# base_station.net
KiCad netlist of a schematic drawn in EAGLE
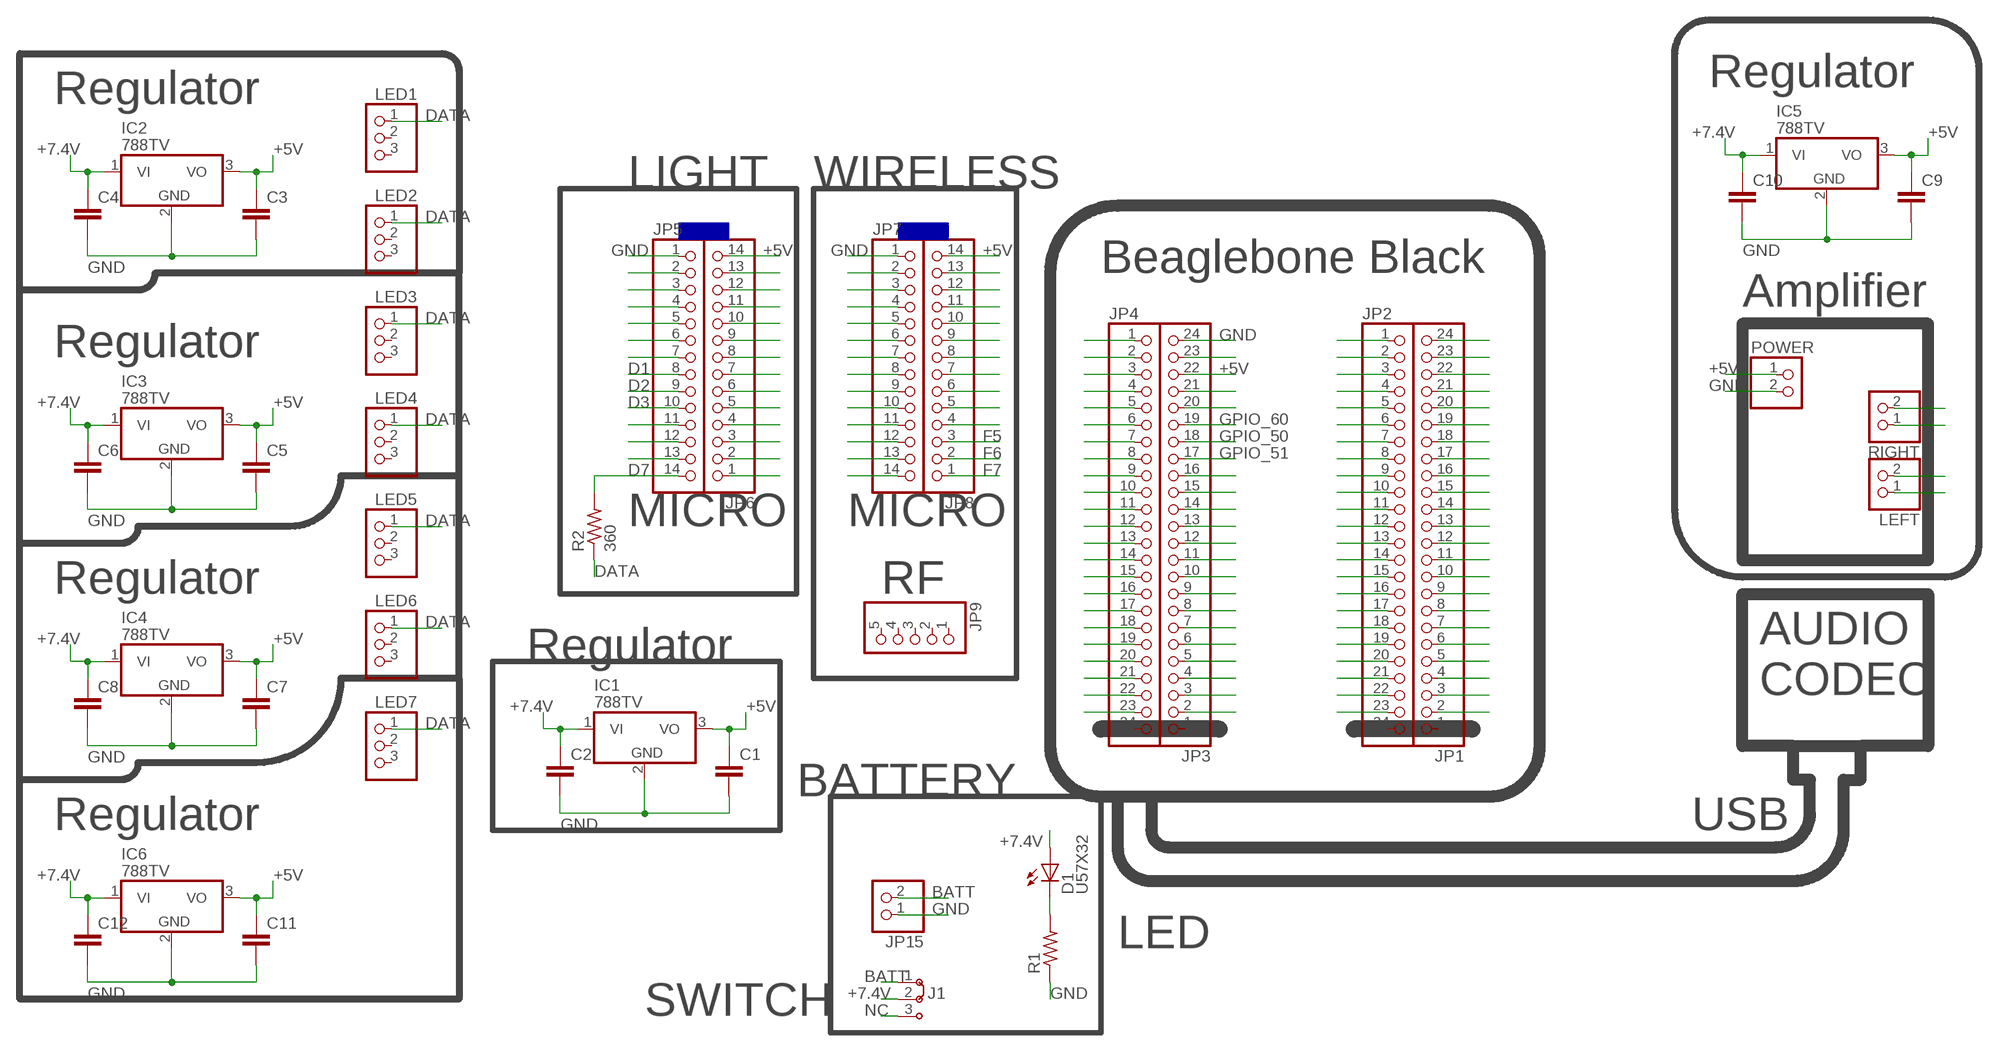
[diagram p0: schematic, sheet 1]

(export (version "E")
  (design (tool "Eeschema 10.0.6"))
  (components
    (comp (ref "C1")
      (value "C2,5-3")
      (footprint "eagle-import:C2.5-3")
      (libsource (lib "eagle-import") (part "C2,5-3"))
    )
    (comp (ref "C2")
      (value "C2,5-3")
      (footprint "eagle-import:C2.5-3")
      (libsource (lib "eagle-import") (part "C2,5-3"))
    )
    (comp (ref "C3")
      (value "C2,5-3")
      (footprint "eagle-import:C2.5-3")
      (libsource (lib "eagle-import") (part "C2,5-3"))
    )
    (comp (ref "C4")
      (value "C2,5-3")
      (footprint "eagle-import:C2.5-3")
      (libsource (lib "eagle-import") (part "C2,5-3"))
    )
    (comp (ref "C5")
      (value "C2,5-3")
      (footprint "eagle-import:C2.5-3")
      (libsource (lib "eagle-import") (part "C2,5-3"))
    )
    (comp (ref "C6")
      (value "C2,5-3")
      (footprint "eagle-import:C2.5-3")
      (libsource (lib "eagle-import") (part "C2,5-3"))
    )
    (comp (ref "C7")
      (value "C2,5-3")
      (footprint "eagle-import:C2.5-3")
      (libsource (lib "eagle-import") (part "C2,5-3"))
    )
    (comp (ref "C8")
      (value "C2,5-3")
      (footprint "eagle-import:C2.5-3")
      (libsource (lib "eagle-import") (part "C2,5-3"))
    )
    (comp (ref "C9")
      (value "C2,5-3")
      (footprint "eagle-import:C2.5-3")
      (libsource (lib "eagle-import") (part "C2,5-3"))
    )
    (comp (ref "C10")
      (value "C2,5-3")
      (footprint "eagle-import:C2.5-3")
      (libsource (lib "eagle-import") (part "C2,5-3"))
    )
    (comp (ref "C11")
      (value "C2,5-3")
      (footprint "eagle-import:C2.5-3")
      (libsource (lib "eagle-import") (part "C2,5-3"))
    )
    (comp (ref "C12")
      (value "C2,5-3")
      (footprint "eagle-import:C2.5-3")
      (libsource (lib "eagle-import") (part "C2,5-3"))
    )
    (comp (ref "D1")
      (value "U57X32")
      (footprint "eagle-import:U57X32")
      (libsource (lib "eagle-import") (part "U57X32"))
    )
    (comp (ref "IC1")
      (value "788TV")
      (footprint "eagle-import:TO220V")
      (libsource (lib "eagle-import") (part "78TV8"))
    )
    (comp (ref "IC2")
      (value "788TV")
      (footprint "eagle-import:TO220V")
      (libsource (lib "eagle-import") (part "78TV8"))
    )
    (comp (ref "IC3")
      (value "788TV")
      (footprint "eagle-import:TO220V")
      (libsource (lib "eagle-import") (part "78TV8"))
    )
    (comp (ref "IC4")
      (value "788TV")
      (footprint "eagle-import:TO220V")
      (libsource (lib "eagle-import") (part "78TV8"))
    )
    (comp (ref "IC5")
      (value "788TV")
      (footprint "eagle-import:TO220V")
      (libsource (lib "eagle-import") (part "78TV8"))
    )
    (comp (ref "IC6")
      (value "788TV")
      (footprint "eagle-import:TO220V")
      (libsource (lib "eagle-import") (part "78TV8"))
    )
    (comp (ref "J1")
      (value "J2X2MM")
      (footprint "eagle-import:04C")
      (libsource (lib "eagle-import") (part "J2X2MM"))
    )
    (comp (ref "JP1")
      (value "PINHD-1X24")
      (footprint "eagle-import:1X24")
      (libsource (lib "eagle-import") (part "PINHD-1X24"))
    )
    (comp (ref "JP2")
      (value "PINHD-1X24")
      (footprint "eagle-import:1X24")
      (libsource (lib "eagle-import") (part "PINHD-1X24"))
    )
    (comp (ref "JP3")
      (value "PINHD-1X24")
      (footprint "eagle-import:1X24")
      (libsource (lib "eagle-import") (part "PINHD-1X24"))
    )
    (comp (ref "JP4")
      (value "PINHD-1X24")
      (footprint "eagle-import:1X24")
      (libsource (lib "eagle-import") (part "PINHD-1X24"))
    )
    (comp (ref "JP5")
      (value "PINHD-1X14")
      (footprint "eagle-import:1X14")
      (libsource (lib "eagle-import") (part "PINHD-1X14"))
    )
    (comp (ref "JP6")
      (value "PINHD-1X14")
      (footprint "eagle-import:1X14")
      (libsource (lib "eagle-import") (part "PINHD-1X14"))
    )
    (comp (ref "JP7")
      (value "PINHD-1X14")
      (footprint "eagle-import:1X14")
      (libsource (lib "eagle-import") (part "PINHD-1X14"))
    )
    (comp (ref "JP8")
      (value "PINHD-1X14")
      (footprint "eagle-import:1X14")
      (libsource (lib "eagle-import") (part "PINHD-1X14"))
    )
    (comp (ref "JP9")
      (value "PINHD-1X5")
      (footprint "eagle-import:1X05")
      (libsource (lib "eagle-import") (part "PINHD-1X5"))
    )
    (comp (ref "JP15")
      (value "PINHD-1X2")
      (footprint "eagle-import:1X02")
      (libsource (lib "eagle-import") (part "PINHD-1X2"))
    )
    (comp (ref "LED1")
      (value "PINHD-1X3")
      (footprint "eagle-import:1X03")
      (libsource (lib "eagle-import") (part "PINHD-1X3"))
    )
    (comp (ref "LED2")
      (value "PINHD-1X3")
      (footprint "eagle-import:1X03")
      (libsource (lib "eagle-import") (part "PINHD-1X3"))
    )
    (comp (ref "LED3")
      (value "PINHD-1X3")
      (footprint "eagle-import:1X03")
      (libsource (lib "eagle-import") (part "PINHD-1X3"))
    )
    (comp (ref "LED4")
      (value "PINHD-1X3")
      (footprint "eagle-import:1X03")
      (libsource (lib "eagle-import") (part "PINHD-1X3"))
    )
    (comp (ref "LED5")
      (value "PINHD-1X3")
      (footprint "eagle-import:1X03")
      (libsource (lib "eagle-import") (part "PINHD-1X3"))
    )
    (comp (ref "LED6")
      (value "PINHD-1X3")
      (footprint "eagle-import:1X03")
      (libsource (lib "eagle-import") (part "PINHD-1X3"))
    )
    (comp (ref "LED7")
      (value "PINHD-1X3")
      (footprint "eagle-import:1X03")
      (libsource (lib "eagle-import") (part "PINHD-1X3"))
    )
    (comp (ref "LEFT")
      (value "PINHD-1X2")
      (footprint "eagle-import:1X02")
      (libsource (lib "eagle-import") (part "PINHD-1X2"))
    )
    (comp (ref "POWER")
      (value "PINHD-1X2")
      (footprint "eagle-import:1X02")
      (libsource (lib "eagle-import") (part "PINHD-1X2"))
    )
    (comp (ref "R1")
      (value "R-US_0204/2V")
      (footprint "eagle-import:0204V")
      (libsource (lib "eagle-import") (part "R-US_0204/2V"))
    )
    (comp (ref "R2")
      (value "360")
      (footprint "eagle-import:0204V")
      (libsource (lib "eagle-import") (part "R-US_0204/2V"))
    )
    (comp (ref "RIGHT")
      (value "PINHD-1X2")
      (footprint "eagle-import:1X02")
      (libsource (lib "eagle-import") (part "PINHD-1X2"))
    )
  )
  (nets
    (net (code "1") (name "/+5V") (class "Default")
      (node (ref "C1") (pin "1") (pinfunction "1_1") (pintype "passive"))
      (node (ref "C11") (pin "1") (pinfunction "1_1") (pintype "passive"))
      (node (ref "C3") (pin "1") (pinfunction "1_1") (pintype "passive"))
      (node (ref "C5") (pin "1") (pinfunction "1_1") (pintype "passive"))
      (node (ref "C7") (pin "1") (pinfunction "1_1") (pintype "passive"))
      (node (ref "C9") (pin "1") (pinfunction "1_1") (pintype "passive"))
      (node (ref "IC1") (pin "3") (pinfunction "VO_3") (pintype "passive"))
      (node (ref "IC2") (pin "3") (pinfunction "VO_3") (pintype "passive"))
      (node (ref "IC3") (pin "3") (pinfunction "VO_3") (pintype "passive"))
      (node (ref "IC4") (pin "3") (pinfunction "VO_3") (pintype "passive"))
      (node (ref "IC5") (pin "3") (pinfunction "VO_3") (pintype "passive"))
      (node (ref "IC6") (pin "3") (pinfunction "VO_3") (pintype "passive"))
      (node (ref "JP3") (pin "22") (pinfunction "22_22") (pintype "passive"))
      (node (ref "JP6") (pin "14") (pinfunction "14_14") (pintype "passive"))
      (node (ref "JP8") (pin "14") (pinfunction "14_14") (pintype "passive"))
      (node (ref "POWER") (pin "1") (pinfunction "1_1") (pintype "passive"))
    )
    (net (code "2") (name "/+7.4V") (class "Default")
      (node (ref "C10") (pin "1") (pinfunction "1_1") (pintype "passive"))
      (node (ref "C12") (pin "1") (pinfunction "1_1") (pintype "passive"))
      (node (ref "C2") (pin "1") (pinfunction "1_1") (pintype "passive"))
      (node (ref "C4") (pin "1") (pinfunction "1_1") (pintype "passive"))
      (node (ref "C6") (pin "1") (pinfunction "1_1") (pintype "passive"))
      (node (ref "C8") (pin "1") (pinfunction "1_1") (pintype "passive"))
      (node (ref "D1") (pin "A") (pinfunction "A_A") (pintype "passive"))
      (node (ref "IC1") (pin "1") (pinfunction "VI_1") (pintype "input"))
      (node (ref "IC2") (pin "1") (pinfunction "VI_1") (pintype "input"))
      (node (ref "IC3") (pin "1") (pinfunction "VI_1") (pintype "input"))
      (node (ref "IC4") (pin "1") (pinfunction "VI_1") (pintype "input"))
      (node (ref "IC5") (pin "1") (pinfunction "VI_1") (pintype "input"))
      (node (ref "IC6") (pin "1") (pinfunction "VI_1") (pintype "input"))
      (node (ref "J1") (pin "2") (pinfunction "2_2") (pintype "passive"))
    )
    (net (code "3") (name "/BATT") (class "Default")
      (node (ref "J1") (pin "1") (pinfunction "1_1") (pintype "passive"))
      (node (ref "JP15") (pin "2") (pinfunction "2_2") (pintype "passive"))
    )
    (net (code "4") (name "/D0") (class "Default")
      (node (ref "JP5") (pin "7") (pinfunction "7_7") (pintype "passive"))
      (node (ref "JP7") (pin "7") (pinfunction "7_7") (pintype "passive"))
    )
    (net (code "5") (name "/D1") (class "Default")
      (node (ref "JP5") (pin "8") (pinfunction "8_8") (pintype "passive"))
      (node (ref "JP7") (pin "8") (pinfunction "8_8") (pintype "passive"))
    )
    (net (code "6") (name "/D2") (class "Default")
      (node (ref "JP5") (pin "9") (pinfunction "9_9") (pintype "passive"))
      (node (ref "JP7") (pin "9") (pinfunction "9_9") (pintype "passive"))
    )
    (net (code "7") (name "/D3") (class "Default")
      (node (ref "JP5") (pin "10") (pinfunction "10_10") (pintype "passive"))
    )
    (net (code "8") (name "/D7") (class "Default")
      (node (ref "JP5") (pin "14") (pinfunction "14_14") (pintype "passive"))
      (node (ref "R2") (pin "2") (pinfunction "2_2") (pintype "passive"))
    )
    (net (code "9") (name "/DATA") (class "Default")
      (node (ref "LED1") (pin "1") (pinfunction "1_1") (pintype "passive"))
      (node (ref "LED2") (pin "1") (pinfunction "1_1") (pintype "passive"))
      (node (ref "LED3") (pin "1") (pinfunction "1_1") (pintype "passive"))
      (node (ref "LED4") (pin "1") (pinfunction "1_1") (pintype "passive"))
      (node (ref "LED5") (pin "1") (pinfunction "1_1") (pintype "passive"))
      (node (ref "LED6") (pin "1") (pinfunction "1_1") (pintype "passive"))
      (node (ref "LED7") (pin "1") (pinfunction "1_1") (pintype "passive"))
      (node (ref "R2") (pin "1") (pinfunction "1_1") (pintype "passive"))
    )
    (net (code "10") (name "/F5") (class "Default")
      (node (ref "JP8") (pin "3") (pinfunction "3_3") (pintype "passive"))
    )
    (net (code "11") (name "/F6") (class "Default")
      (node (ref "JP8") (pin "2") (pinfunction "2_2") (pintype "passive"))
    )
    (net (code "12") (name "/F7") (class "Default")
      (node (ref "JP8") (pin "1") (pinfunction "1_1") (pintype "passive"))
    )
    (net (code "13") (name "/GND") (class "Default")
      (node (ref "C1") (pin "2") (pinfunction "2_2") (pintype "passive"))
      (node (ref "C10") (pin "2") (pinfunction "2_2") (pintype "passive"))
      (node (ref "C11") (pin "2") (pinfunction "2_2") (pintype "passive"))
      (node (ref "C12") (pin "2") (pinfunction "2_2") (pintype "passive"))
      (node (ref "C2") (pin "2") (pinfunction "2_2") (pintype "passive"))
      (node (ref "C3") (pin "2") (pinfunction "2_2") (pintype "passive"))
      (node (ref "C4") (pin "2") (pinfunction "2_2") (pintype "passive"))
      (node (ref "C5") (pin "2") (pinfunction "2_2") (pintype "passive"))
      (node (ref "C6") (pin "2") (pinfunction "2_2") (pintype "passive"))
      (node (ref "C7") (pin "2") (pinfunction "2_2") (pintype "passive"))
      (node (ref "C8") (pin "2") (pinfunction "2_2") (pintype "passive"))
      (node (ref "C9") (pin "2") (pinfunction "2_2") (pintype "passive"))
      (node (ref "IC1") (pin "2") (pinfunction "GND_2") (pintype "passive"))
      (node (ref "IC2") (pin "2") (pinfunction "GND_2") (pintype "passive"))
      (node (ref "IC3") (pin "2") (pinfunction "GND_2") (pintype "passive"))
      (node (ref "IC4") (pin "2") (pinfunction "GND_2") (pintype "passive"))
      (node (ref "IC5") (pin "2") (pinfunction "GND_2") (pintype "passive"))
      (node (ref "IC6") (pin "2") (pinfunction "GND_2") (pintype "passive"))
      (node (ref "JP15") (pin "1") (pinfunction "1_1") (pintype "passive"))
      (node (ref "JP3") (pin "24") (pinfunction "24_24") (pintype "passive"))
      (node (ref "JP5") (pin "1") (pinfunction "1_1") (pintype "passive"))
      (node (ref "JP7") (pin "1") (pinfunction "1_1") (pintype "passive"))
      (node (ref "POWER") (pin "2") (pinfunction "2_2") (pintype "passive"))
      (node (ref "R1") (pin "1") (pinfunction "1_1") (pintype "passive"))
    )
    (net (code "14") (name "/GPIO_50") (class "Default")
      (node (ref "JP3") (pin "18") (pinfunction "18_18") (pintype "passive"))
    )
    (net (code "15") (name "/GPIO_51") (class "Default")
      (node (ref "JP3") (pin "17") (pinfunction "17_17") (pintype "passive"))
    )
    (net (code "16") (name "/GPIO_60") (class "Default")
      (node (ref "JP3") (pin "19") (pinfunction "19_19") (pintype "passive"))
    )
    (net (code "17") (name "/NC") (class "Default")
      (node (ref "J1") (pin "3") (pinfunction "3_3") (pintype "passive"))
    )
    (net (code "18") (name "Net-(D1-C)") (class "Default")
      (node (ref "D1") (pin "K") (pinfunction "C_K") (pintype "passive"))
      (node (ref "R1") (pin "2") (pinfunction "2_2") (pintype "passive"))
    )
    (net (code "19") (name "unconnected-(JP1-Pad1)") (class "Default")
      (node (ref "JP1") (pin "1") (pinfunction "1_1") (pintype "passive"))
    )
    (net (code "20") (name "unconnected-(JP1-Pad2)") (class "Default")
      (node (ref "JP1") (pin "2") (pinfunction "2_2") (pintype "passive"))
    )
    (net (code "21") (name "unconnected-(JP1-Pad3)") (class "Default")
      (node (ref "JP1") (pin "3") (pinfunction "3_3") (pintype "passive"))
    )
    (net (code "22") (name "unconnected-(JP1-Pad4)") (class "Default")
      (node (ref "JP1") (pin "4") (pinfunction "4_4") (pintype "passive"))
    )
    (net (code "23") (name "unconnected-(JP1-Pad5)") (class "Default")
      (node (ref "JP1") (pin "5") (pinfunction "5_5") (pintype "passive"))
    )
    (net (code "24") (name "unconnected-(JP1-Pad6)") (class "Default")
      (node (ref "JP1") (pin "6") (pinfunction "6_6") (pintype "passive"))
    )
    (net (code "25") (name "unconnected-(JP1-Pad7)") (class "Default")
      (node (ref "JP1") (pin "7") (pinfunction "7_7") (pintype "passive"))
    )
    (net (code "26") (name "unconnected-(JP1-Pad8)") (class "Default")
      (node (ref "JP1") (pin "8") (pinfunction "8_8") (pintype "passive"))
    )
    (net (code "27") (name "unconnected-(JP1-Pad9)") (class "Default")
      (node (ref "JP1") (pin "9") (pinfunction "9_9") (pintype "passive"))
    )
    (net (code "28") (name "unconnected-(JP1-Pad10)") (class "Default")
      (node (ref "JP1") (pin "10") (pinfunction "10_10") (pintype "passive"))
    )
    (net (code "29") (name "unconnected-(JP1-Pad11)") (class "Default")
      (node (ref "JP1") (pin "11") (pinfunction "11_11") (pintype "passive"))
    )
    (net (code "30") (name "unconnected-(JP1-Pad12)") (class "Default")
      (node (ref "JP1") (pin "12") (pinfunction "12_12") (pintype "passive"))
    )
    (net (code "31") (name "unconnected-(JP1-Pad13)") (class "Default")
      (node (ref "JP1") (pin "13") (pinfunction "13_13") (pintype "passive"))
    )
    (net (code "32") (name "unconnected-(JP1-Pad14)") (class "Default")
      (node (ref "JP1") (pin "14") (pinfunction "14_14") (pintype "passive"))
    )
    (net (code "33") (name "unconnected-(JP1-Pad15)") (class "Default")
      (node (ref "JP1") (pin "15") (pinfunction "15_15") (pintype "passive"))
    )
    (net (code "34") (name "unconnected-(JP1-Pad16)") (class "Default")
      (node (ref "JP1") (pin "16") (pinfunction "16_16") (pintype "passive"))
    )
    (net (code "35") (name "unconnected-(JP1-Pad17)") (class "Default")
      (node (ref "JP1") (pin "17") (pinfunction "17_17") (pintype "passive"))
    )
    (net (code "36") (name "unconnected-(JP1-Pad18)") (class "Default")
      (node (ref "JP1") (pin "18") (pinfunction "18_18") (pintype "passive"))
    )
    (net (code "37") (name "unconnected-(JP1-Pad19)") (class "Default")
      (node (ref "JP1") (pin "19") (pinfunction "19_19") (pintype "passive"))
    )
    (net (code "38") (name "unconnected-(JP1-Pad20)") (class "Default")
      (node (ref "JP1") (pin "20") (pinfunction "20_20") (pintype "passive"))
    )
    (net (code "39") (name "unconnected-(JP1-Pad21)") (class "Default")
      (node (ref "JP1") (pin "21") (pinfunction "21_21") (pintype "passive"))
    )
    (net (code "40") (name "unconnected-(JP1-Pad22)") (class "Default")
      (node (ref "JP1") (pin "22") (pinfunction "22_22") (pintype "passive"))
    )
    (net (code "41") (name "unconnected-(JP1-Pad23)") (class "Default")
      (node (ref "JP1") (pin "23") (pinfunction "23_23") (pintype "passive"))
    )
    (net (code "42") (name "unconnected-(JP1-Pad24)") (class "Default")
      (node (ref "JP1") (pin "24") (pinfunction "24_24") (pintype "passive"))
    )
    (net (code "43") (name "unconnected-(JP2-Pad1)") (class "Default")
      (node (ref "JP2") (pin "1") (pinfunction "1_1") (pintype "passive"))
    )
    (net (code "44") (name "unconnected-(JP2-Pad2)") (class "Default")
      (node (ref "JP2") (pin "2") (pinfunction "2_2") (pintype "passive"))
    )
    (net (code "45") (name "unconnected-(JP2-Pad3)") (class "Default")
      (node (ref "JP2") (pin "3") (pinfunction "3_3") (pintype "passive"))
    )
    (net (code "46") (name "unconnected-(JP2-Pad4)") (class "Default")
      (node (ref "JP2") (pin "4") (pinfunction "4_4") (pintype "passive"))
    )
    (net (code "47") (name "unconnected-(JP2-Pad5)") (class "Default")
      (node (ref "JP2") (pin "5") (pinfunction "5_5") (pintype "passive"))
    )
    (net (code "48") (name "unconnected-(JP2-Pad6)") (class "Default")
      (node (ref "JP2") (pin "6") (pinfunction "6_6") (pintype "passive"))
    )
    (net (code "49") (name "unconnected-(JP2-Pad7)") (class "Default")
      (node (ref "JP2") (pin "7") (pinfunction "7_7") (pintype "passive"))
    )
    (net (code "50") (name "unconnected-(JP2-Pad8)") (class "Default")
      (node (ref "JP2") (pin "8") (pinfunction "8_8") (pintype "passive"))
    )
    (net (code "51") (name "unconnected-(JP2-Pad9)") (class "Default")
      (node (ref "JP2") (pin "9") (pinfunction "9_9") (pintype "passive"))
    )
    (net (code "52") (name "unconnected-(JP2-Pad10)") (class "Default")
      (node (ref "JP2") (pin "10") (pinfunction "10_10") (pintype "passive"))
    )
    (net (code "53") (name "unconnected-(JP2-Pad11)") (class "Default")
      (node (ref "JP2") (pin "11") (pinfunction "11_11") (pintype "passive"))
    )
    (net (code "54") (name "unconnected-(JP2-Pad12)") (class "Default")
      (node (ref "JP2") (pin "12") (pinfunction "12_12") (pintype "passive"))
    )
    (net (code "55") (name "unconnected-(JP2-Pad13)") (class "Default")
      (node (ref "JP2") (pin "13") (pinfunction "13_13") (pintype "passive"))
    )
    (net (code "56") (name "unconnected-(JP2-Pad14)") (class "Default")
      (node (ref "JP2") (pin "14") (pinfunction "14_14") (pintype "passive"))
    )
    (net (code "57") (name "unconnected-(JP2-Pad15)") (class "Default")
      (node (ref "JP2") (pin "15") (pinfunction "15_15") (pintype "passive"))
    )
    (net (code "58") (name "unconnected-(JP2-Pad16)") (class "Default")
      (node (ref "JP2") (pin "16") (pinfunction "16_16") (pintype "passive"))
    )
    (net (code "59") (name "unconnected-(JP2-Pad17)") (class "Default")
      (node (ref "JP2") (pin "17") (pinfunction "17_17") (pintype "passive"))
    )
    (net (code "60") (name "unconnected-(JP2-Pad18)") (class "Default")
      (node (ref "JP2") (pin "18") (pinfunction "18_18") (pintype "passive"))
    )
    (net (code "61") (name "unconnected-(JP2-Pad19)") (class "Default")
      (node (ref "JP2") (pin "19") (pinfunction "19_19") (pintype "passive"))
    )
    (net (code "62") (name "unconnected-(JP2-Pad20)") (class "Default")
      (node (ref "JP2") (pin "20") (pinfunction "20_20") (pintype "passive"))
    )
    (net (code "63") (name "unconnected-(JP2-Pad21)") (class "Default")
      (node (ref "JP2") (pin "21") (pinfunction "21_21") (pintype "passive"))
    )
    (net (code "64") (name "unconnected-(JP2-Pad22)") (class "Default")
      (node (ref "JP2") (pin "22") (pinfunction "22_22") (pintype "passive"))
    )
    (net (code "65") (name "unconnected-(JP2-Pad23)") (class "Default")
      (node (ref "JP2") (pin "23") (pinfunction "23_23") (pintype "passive"))
    )
    (net (code "66") (name "unconnected-(JP2-Pad24)") (class "Default")
      (node (ref "JP2") (pin "24") (pinfunction "24_24") (pintype "passive"))
    )
    (net (code "67") (name "unconnected-(JP3-Pad1)") (class "Default")
      (node (ref "JP3") (pin "1") (pinfunction "1_1") (pintype "passive"))
    )
    (net (code "68") (name "unconnected-(JP3-Pad2)") (class "Default")
      (node (ref "JP3") (pin "2") (pinfunction "2_2") (pintype "passive"))
    )
    (net (code "69") (name "unconnected-(JP3-Pad3)") (class "Default")
      (node (ref "JP3") (pin "3") (pinfunction "3_3") (pintype "passive"))
    )
    (net (code "70") (name "unconnected-(JP3-Pad4)") (class "Default")
      (node (ref "JP3") (pin "4") (pinfunction "4_4") (pintype "passive"))
    )
    (net (code "71") (name "unconnected-(JP3-Pad5)") (class "Default")
      (node (ref "JP3") (pin "5") (pinfunction "5_5") (pintype "passive"))
    )
    (net (code "72") (name "unconnected-(JP3-Pad6)") (class "Default")
      (node (ref "JP3") (pin "6") (pinfunction "6_6") (pintype "passive"))
    )
    (net (code "73") (name "unconnected-(JP3-Pad7)") (class "Default")
      (node (ref "JP3") (pin "7") (pinfunction "7_7") (pintype "passive"))
    )
    (net (code "74") (name "unconnected-(JP3-Pad8)") (class "Default")
      (node (ref "JP3") (pin "8") (pinfunction "8_8") (pintype "passive"))
    )
    (net (code "75") (name "unconnected-(JP3-Pad9)") (class "Default")
      (node (ref "JP3") (pin "9") (pinfunction "9_9") (pintype "passive"))
    )
    (net (code "76") (name "unconnected-(JP3-Pad10)") (class "Default")
      (node (ref "JP3") (pin "10") (pinfunction "10_10") (pintype "passive"))
    )
    (net (code "77") (name "unconnected-(JP3-Pad11)") (class "Default")
      (node (ref "JP3") (pin "11") (pinfunction "11_11") (pintype "passive"))
    )
    (net (code "78") (name "unconnected-(JP3-Pad12)") (class "Default")
      (node (ref "JP3") (pin "12") (pinfunction "12_12") (pintype "passive"))
    )
    (net (code "79") (name "unconnected-(JP3-Pad13)") (class "Default")
      (node (ref "JP3") (pin "13") (pinfunction "13_13") (pintype "passive"))
    )
    (net (code "80") (name "unconnected-(JP3-Pad14)") (class "Default")
      (node (ref "JP3") (pin "14") (pinfunction "14_14") (pintype "passive"))
    )
    (net (code "81") (name "unconnected-(JP3-Pad15)") (class "Default")
      (node (ref "JP3") (pin "15") (pinfunction "15_15") (pintype "passive"))
    )
    (net (code "82") (name "unconnected-(JP3-Pad16)") (class "Default")
      (node (ref "JP3") (pin "16") (pinfunction "16_16") (pintype "passive"))
    )
    (net (code "83") (name "unconnected-(JP3-Pad20)") (class "Default")
      (node (ref "JP3") (pin "20") (pinfunction "20_20") (pintype "passive"))
    )
    (net (code "84") (name "unconnected-(JP3-Pad21)") (class "Default")
      (node (ref "JP3") (pin "21") (pinfunction "21_21") (pintype "passive"))
    )
    (net (code "85") (name "unconnected-(JP3-Pad23)") (class "Default")
      (node (ref "JP3") (pin "23") (pinfunction "23_23") (pintype "passive"))
    )
    (net (code "86") (name "unconnected-(JP4-Pad1)") (class "Default")
      (node (ref "JP4") (pin "1") (pinfunction "1_1") (pintype "passive"))
    )
    (net (code "87") (name "unconnected-(JP4-Pad2)") (class "Default")
      (node (ref "JP4") (pin "2") (pinfunction "2_2") (pintype "passive"))
    )
    (net (code "88") (name "unconnected-(JP4-Pad3)") (class "Default")
      (node (ref "JP4") (pin "3") (pinfunction "3_3") (pintype "passive"))
    )
    (net (code "89") (name "unconnected-(JP4-Pad4)") (class "Default")
      (node (ref "JP4") (pin "4") (pinfunction "4_4") (pintype "passive"))
    )
    (net (code "90") (name "unconnected-(JP4-Pad5)") (class "Default")
      (node (ref "JP4") (pin "5") (pinfunction "5_5") (pintype "passive"))
    )
    (net (code "91") (name "unconnected-(JP4-Pad6)") (class "Default")
      (node (ref "JP4") (pin "6") (pinfunction "6_6") (pintype "passive"))
    )
    (net (code "92") (name "unconnected-(JP4-Pad7)") (class "Default")
      (node (ref "JP4") (pin "7") (pinfunction "7_7") (pintype "passive"))
    )
    (net (code "93") (name "unconnected-(JP4-Pad8)") (class "Default")
      (node (ref "JP4") (pin "8") (pinfunction "8_8") (pintype "passive"))
    )
    (net (code "94") (name "unconnected-(JP4-Pad9)") (class "Default")
      (node (ref "JP4") (pin "9") (pinfunction "9_9") (pintype "passive"))
    )
    (net (code "95") (name "unconnected-(JP4-Pad10)") (class "Default")
      (node (ref "JP4") (pin "10") (pinfunction "10_10") (pintype "passive"))
    )
    (net (code "96") (name "unconnected-(JP4-Pad11)") (class "Default")
      (node (ref "JP4") (pin "11") (pinfunction "11_11") (pintype "passive"))
    )
    (net (code "97") (name "unconnected-(JP4-Pad12)") (class "Default")
      (node (ref "JP4") (pin "12") (pinfunction "12_12") (pintype "passive"))
    )
    (net (code "98") (name "unconnected-(JP4-Pad13)") (class "Default")
      (node (ref "JP4") (pin "13") (pinfunction "13_13") (pintype "passive"))
    )
    (net (code "99") (name "unconnected-(JP4-Pad14)") (class "Default")
      (node (ref "JP4") (pin "14") (pinfunction "14_14") (pintype "passive"))
    )
    (net (code "100") (name "unconnected-(JP4-Pad15)") (class "Default")
      (node (ref "JP4") (pin "15") (pinfunction "15_15") (pintype "passive"))
    )
    (net (code "101") (name "unconnected-(JP4-Pad16)") (class "Default")
      (node (ref "JP4") (pin "16") (pinfunction "16_16") (pintype "passive"))
    )
    (net (code "102") (name "unconnected-(JP4-Pad17)") (class "Default")
      (node (ref "JP4") (pin "17") (pinfunction "17_17") (pintype "passive"))
    )
    (net (code "103") (name "unconnected-(JP4-Pad18)") (class "Default")
      (node (ref "JP4") (pin "18") (pinfunction "18_18") (pintype "passive"))
    )
    (net (code "104") (name "unconnected-(JP4-Pad19)") (class "Default")
      (node (ref "JP4") (pin "19") (pinfunction "19_19") (pintype "passive"))
    )
    (net (code "105") (name "unconnected-(JP4-Pad20)") (class "Default")
      (node (ref "JP4") (pin "20") (pinfunction "20_20") (pintype "passive"))
    )
    (net (code "106") (name "unconnected-(JP4-Pad21)") (class "Default")
      (node (ref "JP4") (pin "21") (pinfunction "21_21") (pintype "passive"))
    )
    (net (code "107") (name "unconnected-(JP4-Pad22)") (class "Default")
      (node (ref "JP4") (pin "22") (pinfunction "22_22") (pintype "passive"))
    )
    (net (code "108") (name "unconnected-(JP4-Pad23)") (class "Default")
      (node (ref "JP4") (pin "23") (pinfunction "23_23") (pintype "passive"))
    )
    (net (code "109") (name "unconnected-(JP4-Pad24)") (class "Default")
      (node (ref "JP4") (pin "24") (pinfunction "24_24") (pintype "passive"))
    )
    (net (code "110") (name "unconnected-(JP5-Pad2)") (class "Default")
      (node (ref "JP5") (pin "2") (pinfunction "2_2") (pintype "passive"))
    )
    (net (code "111") (name "unconnected-(JP5-Pad3)") (class "Default")
      (node (ref "JP5") (pin "3") (pinfunction "3_3") (pintype "passive"))
    )
    (net (code "112") (name "unconnected-(JP5-Pad4)") (class "Default")
      (node (ref "JP5") (pin "4") (pinfunction "4_4") (pintype "passive"))
    )
    (net (code "113") (name "unconnected-(JP5-Pad5)") (class "Default")
      (node (ref "JP5") (pin "5") (pinfunction "5_5") (pintype "passive"))
    )
    (net (code "114") (name "unconnected-(JP5-Pad6)") (class "Default")
      (node (ref "JP5") (pin "6") (pinfunction "6_6") (pintype "passive"))
    )
    (net (code "115") (name "unconnected-(JP5-Pad11)") (class "Default")
      (node (ref "JP5") (pin "11") (pinfunction "11_11") (pintype "passive"))
    )
    (net (code "116") (name "unconnected-(JP5-Pad12)") (class "Default")
      (node (ref "JP5") (pin "12") (pinfunction "12_12") (pintype "passive"))
    )
    (net (code "117") (name "unconnected-(JP5-Pad13)") (class "Default")
      (node (ref "JP5") (pin "13") (pinfunction "13_13") (pintype "passive"))
    )
    (net (code "118") (name "unconnected-(JP6-Pad1)") (class "Default")
      (node (ref "JP6") (pin "1") (pinfunction "1_1") (pintype "passive"))
    )
    (net (code "119") (name "unconnected-(JP6-Pad2)") (class "Default")
      (node (ref "JP6") (pin "2") (pinfunction "2_2") (pintype "passive"))
    )
    (net (code "120") (name "unconnected-(JP6-Pad3)") (class "Default")
      (node (ref "JP6") (pin "3") (pinfunction "3_3") (pintype "passive"))
    )
    (net (code "121") (name "unconnected-(JP6-Pad4)") (class "Default")
      (node (ref "JP6") (pin "4") (pinfunction "4_4") (pintype "passive"))
    )
    (net (code "122") (name "unconnected-(JP6-Pad5)") (class "Default")
      (node (ref "JP6") (pin "5") (pinfunction "5_5") (pintype "passive"))
    )
    (net (code "123") (name "unconnected-(JP6-Pad6)") (class "Default")
      (node (ref "JP6") (pin "6") (pinfunction "6_6") (pintype "passive"))
    )
    (net (code "124") (name "unconnected-(JP6-Pad7)") (class "Default")
      (node (ref "JP6") (pin "7") (pinfunction "7_7") (pintype "passive"))
    )
    (net (code "125") (name "unconnected-(JP6-Pad8)") (class "Default")
      (node (ref "JP6") (pin "8") (pinfunction "8_8") (pintype "passive"))
    )
    (net (code "126") (name "unconnected-(JP6-Pad9)") (class "Default")
      (node (ref "JP6") (pin "9") (pinfunction "9_9") (pintype "passive"))
    )
    (net (code "127") (name "unconnected-(JP6-Pad10)") (class "Default")
      (node (ref "JP6") (pin "10") (pinfunction "10_10") (pintype "passive"))
    )
    (net (code "128") (name "unconnected-(JP6-Pad11)") (class "Default")
      (node (ref "JP6") (pin "11") (pinfunction "11_11") (pintype "passive"))
    )
    (net (code "129") (name "unconnected-(JP6-Pad12)") (class "Default")
      (node (ref "JP6") (pin "12") (pinfunction "12_12") (pintype "passive"))
    )
    (net (code "130") (name "unconnected-(JP6-Pad13)") (class "Default")
      (node (ref "JP6") (pin "13") (pinfunction "13_13") (pintype "passive"))
    )
    (net (code "131") (name "unconnected-(JP7-Pad2)") (class "Default")
      (node (ref "JP7") (pin "2") (pinfunction "2_2") (pintype "passive"))
    )
    (net (code "132") (name "unconnected-(JP7-Pad3)") (class "Default")
      (node (ref "JP7") (pin "3") (pinfunction "3_3") (pintype "passive"))
    )
    (net (code "133") (name "unconnected-(JP7-Pad4)") (class "Default")
      (node (ref "JP7") (pin "4") (pinfunction "4_4") (pintype "passive"))
    )
    (net (code "134") (name "unconnected-(JP7-Pad5)") (class "Default")
      (node (ref "JP7") (pin "5") (pinfunction "5_5") (pintype "passive"))
    )
    (net (code "135") (name "unconnected-(JP7-Pad6)") (class "Default")
      (node (ref "JP7") (pin "6") (pinfunction "6_6") (pintype "passive"))
    )
    (net (code "136") (name "unconnected-(JP7-Pad10)") (class "Default")
      (node (ref "JP7") (pin "10") (pinfunction "10_10") (pintype "passive"))
    )
    (net (code "137") (name "unconnected-(JP7-Pad11)") (class "Default")
      (node (ref "JP7") (pin "11") (pinfunction "11_11") (pintype "passive"))
    )
    (net (code "138") (name "unconnected-(JP7-Pad12)") (class "Default")
      (node (ref "JP7") (pin "12") (pinfunction "12_12") (pintype "passive"))
    )
    (net (code "139") (name "unconnected-(JP7-Pad13)") (class "Default")
      (node (ref "JP7") (pin "13") (pinfunction "13_13") (pintype "passive"))
    )
    (net (code "140") (name "unconnected-(JP7-Pad14)") (class "Default")
      (node (ref "JP7") (pin "14") (pinfunction "14_14") (pintype "passive"))
    )
    (net (code "141") (name "unconnected-(JP8-Pad4)") (class "Default")
      (node (ref "JP8") (pin "4") (pinfunction "4_4") (pintype "passive"))
    )
    (net (code "142") (name "unconnected-(JP8-Pad5)") (class "Default")
      (node (ref "JP8") (pin "5") (pinfunction "5_5") (pintype "passive"))
    )
    (net (code "143") (name "unconnected-(JP8-Pad6)") (class "Default")
      (node (ref "JP8") (pin "6") (pinfunction "6_6") (pintype "passive"))
    )
    (net (code "144") (name "unconnected-(JP8-Pad7)") (class "Default")
      (node (ref "JP8") (pin "7") (pinfunction "7_7") (pintype "passive"))
    )
    (net (code "145") (name "unconnected-(JP8-Pad8)") (class "Default")
      (node (ref "JP8") (pin "8") (pinfunction "8_8") (pintype "passive"))
    )
    (net (code "146") (name "unconnected-(JP8-Pad9)") (class "Default")
      (node (ref "JP8") (pin "9") (pinfunction "9_9") (pintype "passive"))
    )
    (net (code "147") (name "unconnected-(JP8-Pad10)") (class "Default")
      (node (ref "JP8") (pin "10") (pinfunction "10_10") (pintype "passive"))
    )
    (net (code "148") (name "unconnected-(JP8-Pad11)") (class "Default")
      (node (ref "JP8") (pin "11") (pinfunction "11_11") (pintype "passive"))
    )
    (net (code "149") (name "unconnected-(JP8-Pad12)") (class "Default")
      (node (ref "JP8") (pin "12") (pinfunction "12_12") (pintype "passive"))
    )
    (net (code "150") (name "unconnected-(JP8-Pad13)") (class "Default")
      (node (ref "JP8") (pin "13") (pinfunction "13_13") (pintype "passive"))
    )
    (net (code "151") (name "unconnected-(JP9-Pad1)") (class "Default")
      (node (ref "JP9") (pin "1") (pinfunction "1_1") (pintype "passive"))
    )
    (net (code "152") (name "unconnected-(JP9-Pad2)") (class "Default")
      (node (ref "JP9") (pin "2") (pinfunction "2_2") (pintype "passive"))
    )
    (net (code "153") (name "unconnected-(JP9-Pad3)") (class "Default")
      (node (ref "JP9") (pin "3") (pinfunction "3_3") (pintype "passive"))
    )
    (net (code "154") (name "unconnected-(JP9-Pad4)") (class "Default")
      (node (ref "JP9") (pin "4") (pinfunction "4_4") (pintype "passive"))
    )
    (net (code "155") (name "unconnected-(JP9-Pad5)") (class "Default")
      (node (ref "JP9") (pin "5") (pinfunction "5_5") (pintype "passive"))
    )
    (net (code "156") (name "unconnected-(LED1-Pad2)") (class "Default")
      (node (ref "LED1") (pin "2") (pinfunction "2_2") (pintype "passive"))
    )
    (net (code "157") (name "unconnected-(LED1-Pad3)") (class "Default")
      (node (ref "LED1") (pin "3") (pinfunction "3_3") (pintype "passive"))
    )
    (net (code "158") (name "unconnected-(LED2-Pad2)") (class "Default")
      (node (ref "LED2") (pin "2") (pinfunction "2_2") (pintype "passive"))
    )
    (net (code "159") (name "unconnected-(LED2-Pad3)") (class "Default")
      (node (ref "LED2") (pin "3") (pinfunction "3_3") (pintype "passive"))
    )
    (net (code "160") (name "unconnected-(LED3-Pad2)") (class "Default")
      (node (ref "LED3") (pin "2") (pinfunction "2_2") (pintype "passive"))
    )
    (net (code "161") (name "unconnected-(LED3-Pad3)") (class "Default")
      (node (ref "LED3") (pin "3") (pinfunction "3_3") (pintype "passive"))
    )
    (net (code "162") (name "unconnected-(LED4-Pad2)") (class "Default")
      (node (ref "LED4") (pin "2") (pinfunction "2_2") (pintype "passive"))
    )
    (net (code "163") (name "unconnected-(LED4-Pad3)") (class "Default")
      (node (ref "LED4") (pin "3") (pinfunction "3_3") (pintype "passive"))
    )
    (net (code "164") (name "unconnected-(LED5-Pad2)") (class "Default")
      (node (ref "LED5") (pin "2") (pinfunction "2_2") (pintype "passive"))
    )
    (net (code "165") (name "unconnected-(LED5-Pad3)") (class "Default")
      (node (ref "LED5") (pin "3") (pinfunction "3_3") (pintype "passive"))
    )
    (net (code "166") (name "unconnected-(LED6-Pad2)") (class "Default")
      (node (ref "LED6") (pin "2") (pinfunction "2_2") (pintype "passive"))
    )
    (net (code "167") (name "unconnected-(LED6-Pad3)") (class "Default")
      (node (ref "LED6") (pin "3") (pinfunction "3_3") (pintype "passive"))
    )
    (net (code "168") (name "unconnected-(LED7-Pad2)") (class "Default")
      (node (ref "LED7") (pin "2") (pinfunction "2_2") (pintype "passive"))
    )
    (net (code "169") (name "unconnected-(LED7-Pad3)") (class "Default")
      (node (ref "LED7") (pin "3") (pinfunction "3_3") (pintype "passive"))
    )
    (net (code "170") (name "unconnected-(LEFT-Pad1)") (class "Default")
      (node (ref "LEFT") (pin "1") (pinfunction "1_1") (pintype "passive"))
    )
    (net (code "171") (name "unconnected-(LEFT-Pad2)") (class "Default")
      (node (ref "LEFT") (pin "2") (pinfunction "2_2") (pintype "passive"))
    )
    (net (code "172") (name "unconnected-(RIGHT-Pad1)") (class "Default")
      (node (ref "RIGHT") (pin "1") (pinfunction "1_1") (pintype "passive"))
    )
    (net (code "173") (name "unconnected-(RIGHT-Pad2)") (class "Default")
      (node (ref "RIGHT") (pin "2") (pinfunction "2_2") (pintype "passive"))
    )
  )
)
